# ad_Simu_Test.net
KiCad netlist of a schematic drawn in Altium Designer
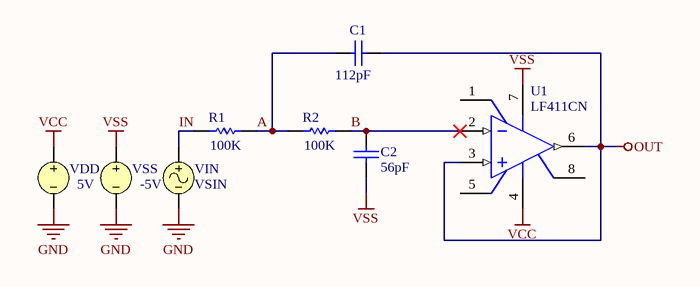
[diagram p0: ad_Simu_Test.SchDoc]

(export (version "E")
  (design (tool "Eeschema 10.0.6"))
  (components
    (comp (ref "C1")
      (value "112pF")
      (footprint "1608[0603]")
      (description "Capacitor (Semiconductor SIM Model)")
      (fields (field (name "Comment") "Cap Semi") (field (name "PUBLISHER") "Altium Limited"))
      (libsource (lib "Miscellaneous Devices") (part "Cap Semi"))
    )
    (comp (ref "C2")
      (value "56pF")
      (footprint "1608[0603]")
      (description "Capacitor (Semiconductor SIM Model)")
      (fields (field (name "Comment") "Cap Semi") (field (name "PUBLISHER") "Altium Limited"))
      (libsource (lib "Miscellaneous Devices") (part "Cap Semi"))
    )
    (comp (ref "R1")
      (value "100K")
      (footprint "AXIAL-0.5")
      (description "Semiconductor Resistor")
      (fields (field (name "Comment") "Res Semi") (field (name "PUBLISHER") "Altium Limited"))
      (libsource (lib "Miscellaneous Devices") (part "Res Semi"))
    )
    (comp (ref "R2")
      (value "100K")
      (footprint "AXIAL-0.5")
      (description "Semiconductor Resistor")
      (fields (field (name "Comment") "Res Semi") (field (name "PUBLISHER") "Altium Limited"))
      (libsource (lib "Miscellaneous Devices") (part "Res Semi"))
    )
    (comp (ref "U1")
      (value "LF411CN")
      (footprint "N08E")
      (description "Low Offset, Low Drift JFET Input Operational Amplifier, 8-pin MDIP")
      (fields
        (field (name "MANUFACTURER") "National Semiconductor")
        (field (name "PUBLISHER") "Altium Limited")
      )
      (libsource (lib "NSC Amplifier") (part "LF411CN"))
    )
    (comp (ref "VDD")
      (value "5V")
      (description "Voltage Source")
      (fields (field (name "Comment") "VSRC") (field (name "PUBLISHER") "Altium Limited"))
      (libsource (lib "Simulation Sources") (part "VSRC"))
    )
    (comp (ref "VIN")
      (value "VSIN")
      (description "Sinusoidal Voltage Source")
      (fields (field (name "PUBLISHER") "Altium Limited"))
      (libsource (lib "Simulation Sources") (part "VSIN"))
    )
    (comp (ref "VSS")
      (value "-5V")
      (description "Voltage Source")
      (fields (field (name "Comment") "VSRC") (field (name "PUBLISHER") "Altium Limited"))
      (libsource (lib "Simulation Sources") (part "VSRC"))
    )
  )
  (nets
    (net (code "1") (name "/A") (class "Default")
      (node (ref "C1") (pin "1") (pinfunction "1_1") (pintype "passive"))
      (node (ref "R1") (pin "2") (pinfunction "2_2") (pintype "passive"))
      (node (ref "R2") (pin "1") (pinfunction "1_1") (pintype "passive"))
    )
    (net (code "2") (name "/B") (class "Default")
      (node (ref "C2") (pin "2") (pinfunction "2_2") (pintype "passive"))
      (node (ref "R2") (pin "2") (pinfunction "2_2") (pintype "passive"))
      (node (ref "U1") (pin "2") (pinfunction "IN-_2") (pintype "input"))
    )
    (net (code "3") (name "/IN") (class "Default")
      (node (ref "R1") (pin "1") (pinfunction "1_1") (pintype "passive"))
      (node (ref "VIN") (pin "1") (pinfunction "1_1") (pintype "passive"))
    )
    (net (code "4") (name "GND") (class "Default")
      (node (ref "VDD") (pin "2") (pinfunction "2_2") (pintype "passive"))
      (node (ref "VIN") (pin "2") (pinfunction "2_2") (pintype "passive"))
      (node (ref "VSS") (pin "2") (pinfunction "2_2") (pintype "passive"))
    )
    (net (code "5") (name "OUT") (class "Default")
      (node (ref "C1") (pin "2") (pinfunction "2_2") (pintype "passive"))
      (node (ref "U1") (pin "3") (pinfunction "IN+_3") (pintype "input"))
      (node (ref "U1") (pin "6") (pinfunction "OUT_6") (pintype "output"))
    )
    (net (code "6") (name "VCC") (class "Default")
      (node (ref "U1") (pin "4") (pinfunction "V-_4") (pintype "power_in"))
      (node (ref "VDD") (pin "1") (pinfunction "1_1") (pintype "passive"))
    )
    (net (code "7") (name "VSS") (class "Default")
      (node (ref "C2") (pin "1") (pinfunction "1_1") (pintype "passive"))
      (node (ref "U1") (pin "7") (pinfunction "V+_7") (pintype "power_in"))
      (node (ref "VSS") (pin "1") (pinfunction "1_1") (pintype "passive"))
    )
    (net (code "8") (name "unconnected-(U1-BAL-Pad1)") (class "Default")
      (node (ref "U1") (pin "1") (pinfunction "BAL_1") (pintype "passive"))
    )
    (net (code "9") (name "unconnected-(U1-BAL-Pad5)") (class "Default")
      (node (ref "U1") (pin "5") (pinfunction "BAL_5") (pintype "passive"))
    )
    (net (code "10") (name "unconnected-(U1-NC-Pad8)") (class "Default")
      (node (ref "U1") (pin "8") (pinfunction "NC_8") (pintype "passive"))
    )
  )
)
